# power_dispatch_v1.net
KiCad netlist of a schematic drawn in EAGLE
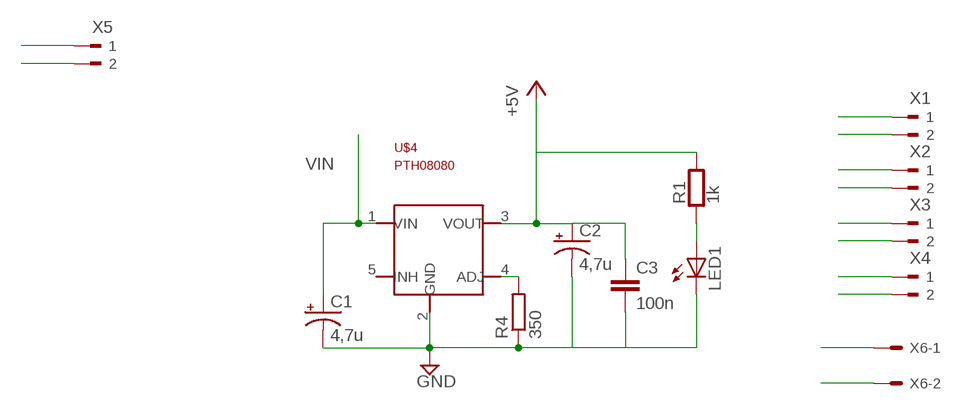
[diagram p0: schematic, sheet 1]

(export (version "E")
  (design (tool "Eeschema 10.0.6"))
  (components
    (comp (ref "C1")
      (value "4,7u")
      (footprint "eagle-import:CPOL-RADIAL-10UF-25V")
      (libsource (lib "eagle-import") (part "CAP_POLPTH2"))
    )
    (comp (ref "C2")
      (value "4,7u")
      (footprint "eagle-import:CPOL-RADIAL-10UF-25V")
      (libsource (lib "eagle-import") (part "CAP_POLPTH2"))
    )
    (comp (ref "C3")
      (value "100n")
      (footprint "eagle-import:CAP-PTH-SMALL2")
      (libsource (lib "eagle-import") (part "CAPPTH2"))
    )
    (comp (ref "LED1")
      (value "LEDSML0805")
      (footprint "eagle-import:SML0805")
      (libsource (lib "eagle-import") (part "LEDSML0805"))
    )
    (comp (ref "R1")
      (value "1k")
      (footprint "eagle-import:0805")
      (libsource (lib "eagle-import") (part "R0805"))
    )
    (comp (ref "R4")
      (value "350")
      (footprint "eagle-import:R0805")
      (libsource (lib "eagle-import") (part "R-EU_R0805"))
    )
    (comp (ref "U$4")
      (value "PTH08080")
      (footprint "eagle-import:PTH08080EUF")
      (libsource (lib "eagle-import") (part "PTH08080"))
    )
    (comp (ref "X1")
      (value "90-2")
      (footprint "eagle-import:90-2")
      (libsource (lib "eagle-import") (part "90-2"))
    )
    (comp (ref "X2")
      (value "90-2")
      (footprint "eagle-import:90-2")
      (libsource (lib "eagle-import") (part "90-2"))
    )
    (comp (ref "X3")
      (value "90-2")
      (footprint "eagle-import:90-2")
      (libsource (lib "eagle-import") (part "90-2"))
    )
    (comp (ref "X4")
      (value "90-2")
      (footprint "eagle-import:90-2")
      (libsource (lib "eagle-import") (part "90-2"))
    )
    (comp (ref "X5")
      (value "90-2")
      (footprint "eagle-import:90-2")
      (libsource (lib "eagle-import") (part "90-2"))
    )
    (comp (ref "X6")
      (value "KK-156-2")
      (footprint "eagle-import:KK-156-2")
      (libsource (lib "eagle-import") (part "KK-156-2"))
    )
  )
  (nets
    (net (code "1") (name "+5V") (class "Default")
      (node (ref "C2") (pin "1") (pinfunction "+_1") (pintype "passive"))
      (node (ref "C3") (pin "1") (pinfunction "1_1") (pintype "passive"))
      (node (ref "R1") (pin "2") (pinfunction "P$2_2") (pintype "passive"))
      (node (ref "U$4") (pin "3") (pinfunction "VOUT_3") (pintype "power_in"))
      (node (ref "X6") (pin "1") (pinfunction "S_1") (pintype "passive"))
    )
    (net (code "2") (name "/VIN") (class "Default")
      (node (ref "C1") (pin "1") (pinfunction "+_1") (pintype "passive"))
      (node (ref "U$4") (pin "1") (pinfunction "VIN_1") (pintype "power_in"))
      (node (ref "X1") (pin "1") (pinfunction "1_1") (pintype "passive"))
      (node (ref "X2") (pin "1") (pinfunction "1_1") (pintype "passive"))
      (node (ref "X3") (pin "1") (pinfunction "1_1") (pintype "passive"))
      (node (ref "X4") (pin "1") (pinfunction "1_1") (pintype "passive"))
      (node (ref "X5") (pin "1") (pinfunction "1_1") (pintype "passive"))
    )
    (net (code "3") (name "GND") (class "Default")
      (node (ref "C1") (pin "2") (pinfunction "-_2") (pintype "passive"))
      (node (ref "C2") (pin "2") (pinfunction "-_2") (pintype "passive"))
      (node (ref "C3") (pin "2") (pinfunction "2_2") (pintype "passive"))
      (node (ref "LED1") (pin "C") (pinfunction "C_C") (pintype "passive"))
      (node (ref "R4") (pin "1") (pinfunction "1_1") (pintype "passive"))
      (node (ref "U$4") (pin "2") (pinfunction "GND_2") (pintype "power_in"))
      (node (ref "X1") (pin "2") (pinfunction "2_2") (pintype "passive"))
      (node (ref "X2") (pin "2") (pinfunction "2_2") (pintype "passive"))
      (node (ref "X3") (pin "2") (pinfunction "2_2") (pintype "passive"))
      (node (ref "X4") (pin "2") (pinfunction "2_2") (pintype "passive"))
      (node (ref "X5") (pin "2") (pinfunction "2_2") (pintype "passive"))
      (node (ref "X6") (pin "2") (pinfunction "S_2") (pintype "passive"))
    )
    (net (code "4") (name "Net-(R1-P$1)") (class "Default")
      (node (ref "LED1") (pin "A") (pinfunction "A_A") (pintype "passive"))
      (node (ref "R1") (pin "1") (pinfunction "P$1_1") (pintype "passive"))
    )
    (net (code "5") (name "Net-(U$4-ADJ)") (class "Default")
      (node (ref "R4") (pin "2") (pinfunction "2_2") (pintype "passive"))
      (node (ref "U$4") (pin "4") (pinfunction "ADJ_4") (pintype "passive"))
    )
    (net (code "6") (name "unconnected-(U$4-INH-Pad5)") (class "Default")
      (node (ref "U$4") (pin "5") (pinfunction "INH_5") (pintype "bidirectional"))
    )
  )
)
